# EasyEDA_Schematic_Split_Flap_Controller_.net
KiCad netlist of a schematic drawn in EasyEDA
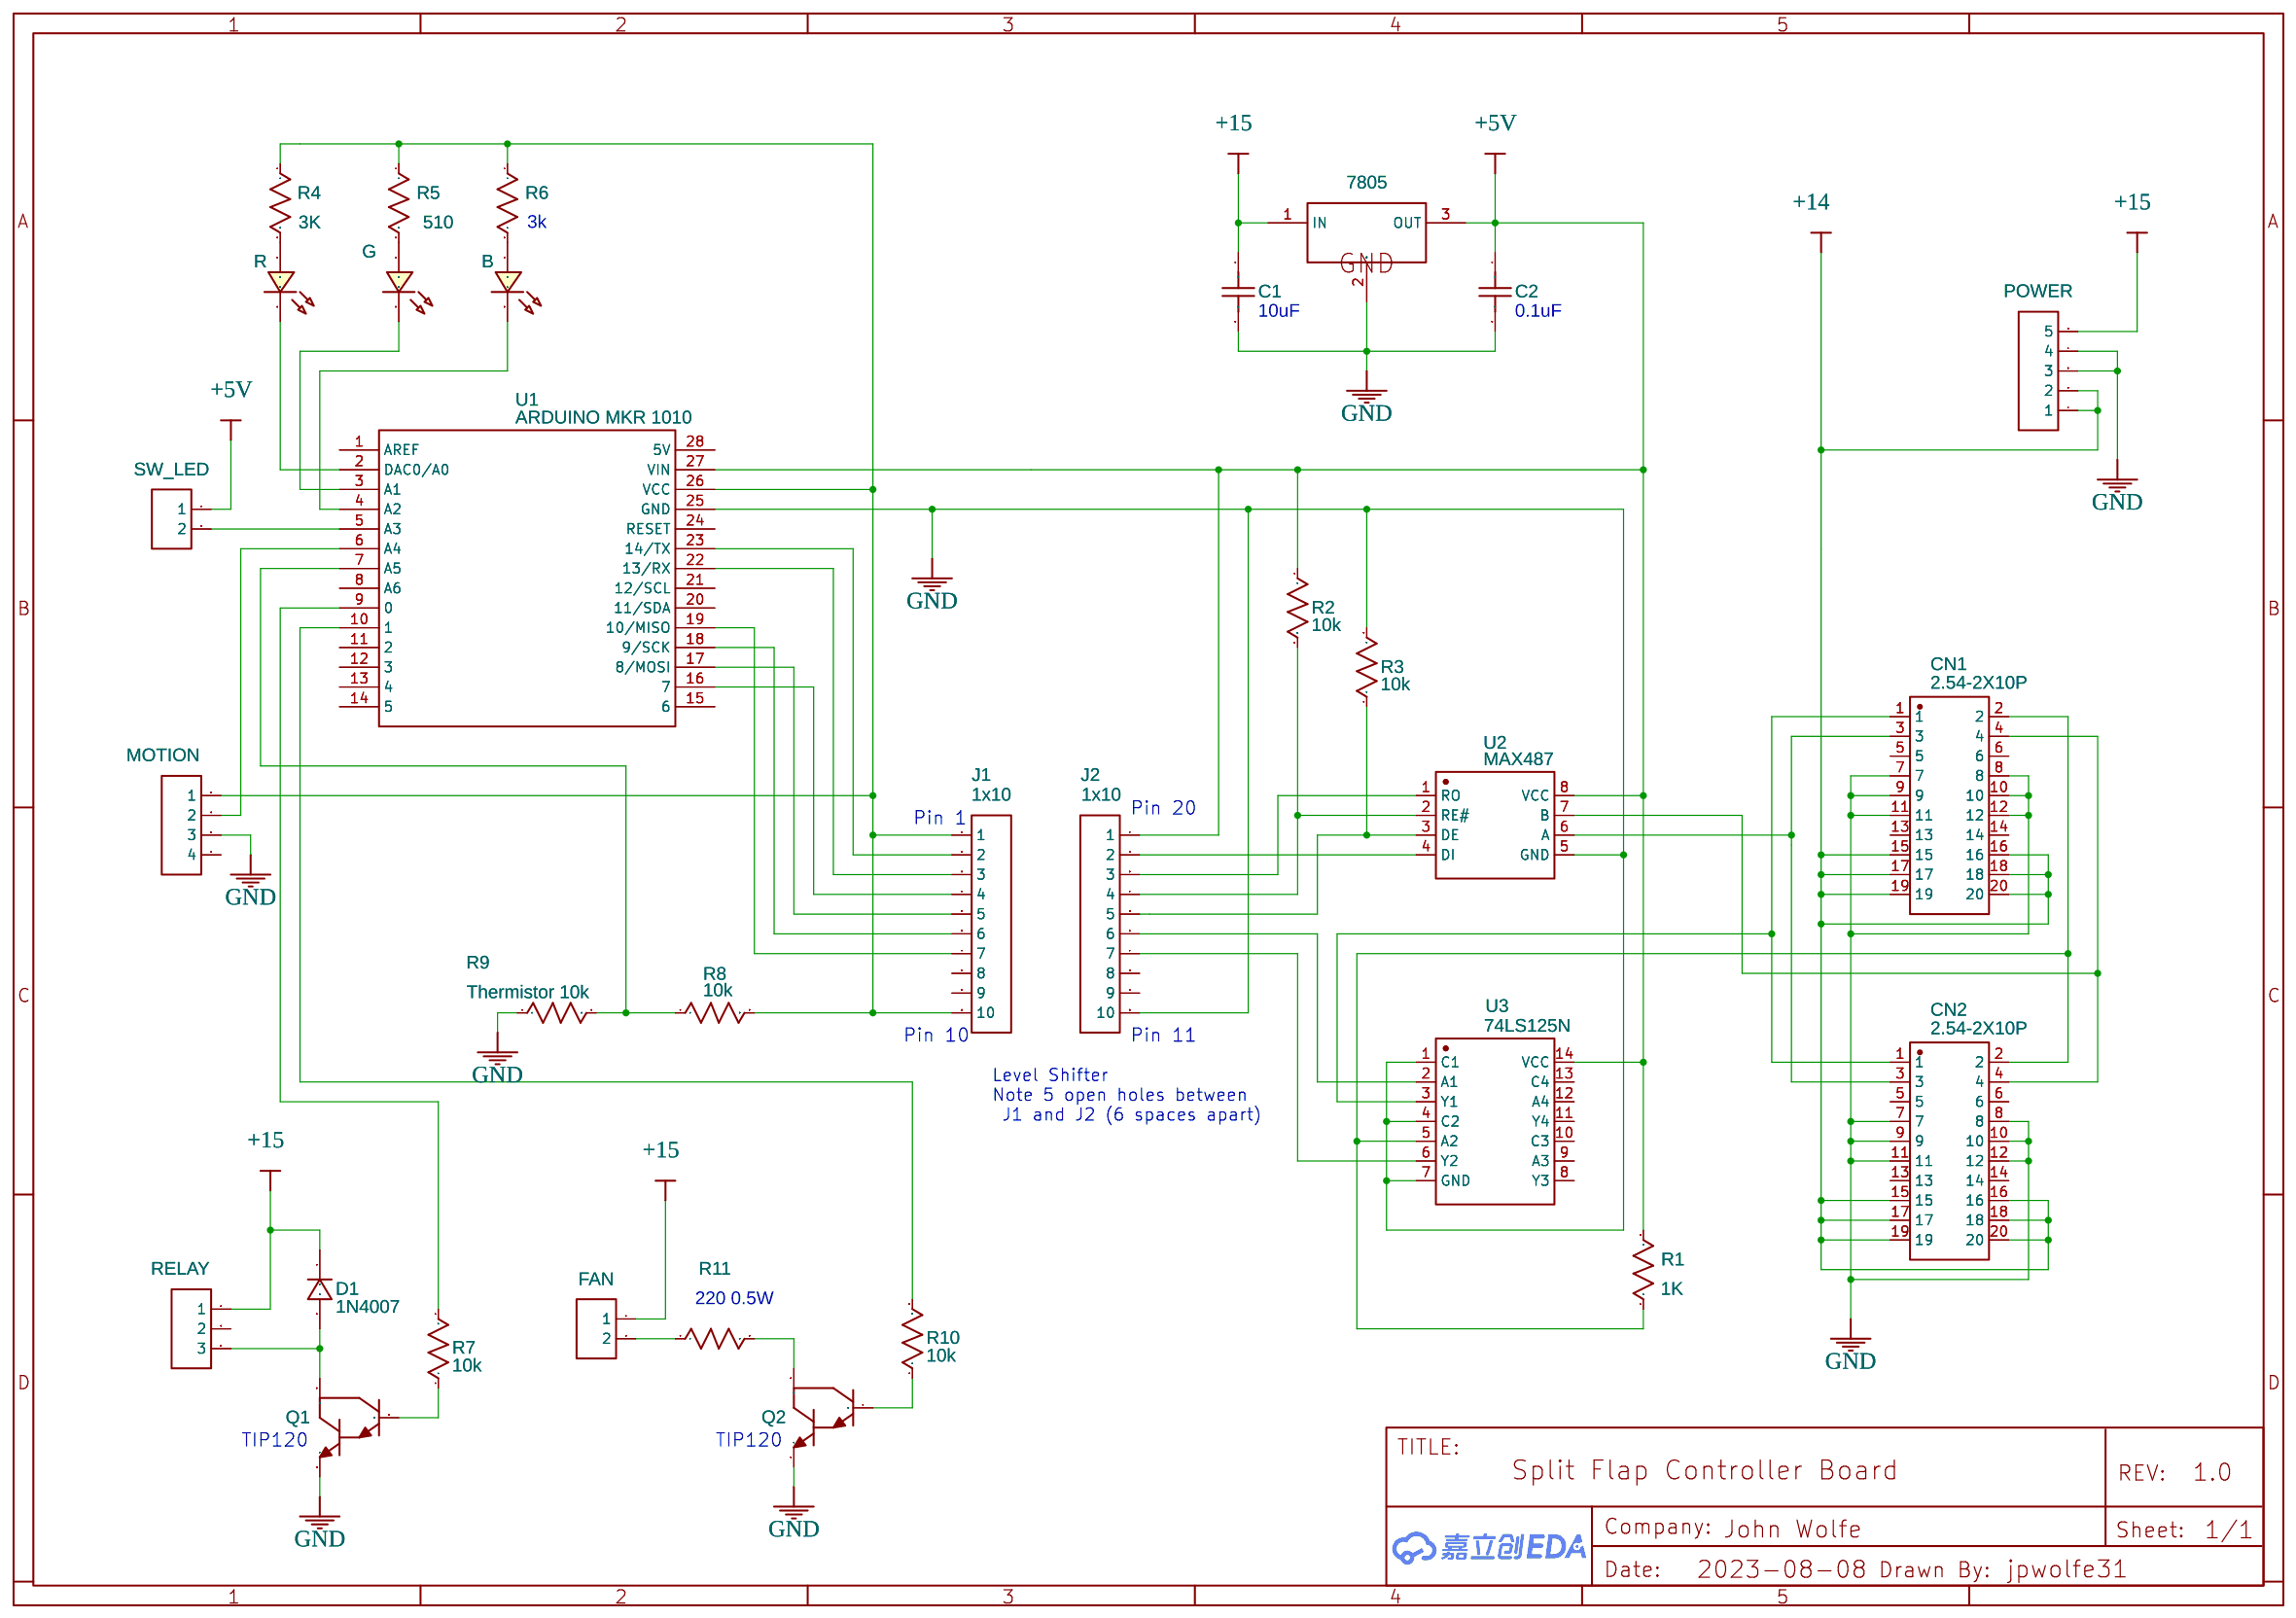
[diagram p0: schematic sheet]

(export (version "E")
  (design (tool "Eeschema 10.0.6"))
  (components
    (comp (ref "1K") (value "R1") (libsource (lib "") (part "R_AXIAL-0.3_US_5")))
    (comp (ref "3K") (value "R5") (libsource (lib "") (part "R_AXIAL-0.3_US_2")))
    (comp (ref "510") (value "R4") (libsource (lib "") (part "R_AXIAL-0.3_US_3")))
    (comp (ref "7805")
      (value "7805")
      (fields
        (field (name "Manufacturer Part") "L7805CV-DG")
        (field (name "Manufacturer") "STMicroelectronics")
      )
      (libsource (lib "") (part "7805(TO-220)"))
    )
    (comp (ref "B")
      (value "LED-TH-3mm_B")
      (fields
        (field (name "Manufacturer Part") "204-10SUBC/S400-A4")
        (field (name "Manufacturer") "EVERLIGHT(台湾亿光)")
      )
      (libsource (lib "") (part "LED-TH-3mm_B"))
    )
    (comp (ref "C1") (value "1u") (libsource (lib "") (part "C_RAD-0.1_US")))
    (comp (ref "C2") (value "1u") (libsource (lib "") (part "C_RAD-0.1_US")))
    (comp (ref "CN1")
      (value "2.54-2X10P")
      (fields
        (field (name "Manufacturer Part") "KH-DC3-2.54-2X10P")
        (field (name "Manufacturer") "kinghelm(金航标)")
      )
      (libsource (lib "") (part "KH-DC3-2.54-2X10P"))
    )
    (comp (ref "CN2")
      (value "2.54-2X10P")
      (fields
        (field (name "Manufacturer Part") "KH-DC3-2.54-2X10P")
        (field (name "Manufacturer") "kinghelm(金航标)")
      )
      (libsource (lib "") (part "KH-DC3-2.54-2X10P"))
    )
    (comp (ref "D1")
      (value "1N4007")
      (fields (field (name "Manufacturer Part") "1N4148") (field (name "Manufacturer") "STMicroelectronics"))
      (libsource (lib "") (part "1N4148"))
    )
    (comp (ref "FAN") (value "HDR-M-2.54_1x2") (libsource (lib "") (part "HDR-M-2.54_1x2_1")))
    (comp (ref "G")
      (value "LED-TH-3mm_G")
      (fields
        (field (name "Manufacturer Part") "204-10SYGD/S530-E3")
        (field (name "Manufacturer") "EVERLIGHT(台湾亿光)")
      )
      (libsource (lib "") (part "LED-TH-3mm_G"))
    )
    (comp (ref "J1")
      (value "1x10")
      (fields (field (name "Manufacturer") "BOOMELE(博穆精密)"))
      (libsource (lib "") (part "Header-Female-2.54_1x10"))
    )
    (comp (ref "J2")
      (value "1x10")
      (fields (field (name "Manufacturer") "BOOMELE(博穆精密)"))
      (libsource (lib "") (part "Header-Female-2.54_1x10_1"))
    )
    (comp (ref "MOTION") (value "HDR-M-2.54_1x4") (libsource (lib "") (part "HDR-M-2.54_1x4")))
    (comp (ref "POWER") (value "CN3") (libsource (lib "") (part "HDR-F-2.54_1x5")))
    (comp (ref "Q1")
      (value "Q1")
      (fields (field (name "Manufacturer") "CJ(江苏长电/长晶)"))
      (libsource (lib "") (part "TIP122_C84073"))
    )
    (comp (ref "Q2")
      (value "TIP120")
      (fields (field (name "Manufacturer") "CJ(江苏长电/长晶)"))
      (libsource (lib "") (part "TIP122_C84073"))
    )
    (comp (ref "R")
      (value "LED-TH-3mm_R")
      (fields
        (field (name "Manufacturer Part") "204-10SDRD/S530-A3-L")
        (field (name "Manufacturer") "EVERLIGHT(台湾亿光)")
      )
      (libsource (lib "") (part "LED-TH-3mm_R"))
    )
    (comp (ref "R2") (value "10k") (libsource (lib "") (part "R_AXIAL-0.3_US_1")))
    (comp (ref "R3") (value "10k") (libsource (lib "") (part "R_AXIAL-0.3_US_4")))
    (comp (ref "R6") (value "R6") (libsource (lib "") (part "R_AXIAL-0.3_US_1")))
    (comp (ref "R7") (value "10k") (libsource (lib "") (part "R_AXIAL-0.3_US_4")))
    (comp (ref "R8") (value "10k") (libsource (lib "") (part "R_AXIAL-0.3_US")))
    (comp (ref "R9") (value "Thermistor 10k") (libsource (lib "") (part "R_AXIAL-0.3_US")))
    (comp (ref "R10") (value "10k") (libsource (lib "") (part "R_AXIAL-0.3_US_4")))
    (comp (ref "R11") (value "R11") (libsource (lib "") (part "R_AXIAL-0.4_US")))
    (comp (ref "RELAY") (value "HDR-M-2.54_1x3") (libsource (lib "") (part "HDR-M-2.54_1x3")))
    (comp (ref "SW_LED") (value "HDR-M-2.54_1x2") (libsource (lib "") (part "HDR-M-2.54_1x2")))
    (comp (ref "U1") (value "ARDUINO MKR 1010") (libsource (lib "") (part "ARDUINO MKR 1010")))
    (comp (ref "U2")
      (value "MAX487")
      (fields (field (name "Manufacturer") "MAXIM"))
      (libsource (lib "") (part "MAX487CPA"))
    )
    (comp (ref "U3") (value "74LS125N") (libsource (lib "") (part "74LS125N")))
  )
  (nets
    (net (code "1") (name "+5V") (class "Default")
      (node (ref "1K") (pin "2") (pinfunction "2_2") (pintype "unspecified"))
      (node (ref "7805") (pin "3") (pinfunction "OUT_3") (pintype "passive"))
      (node (ref "C2") (pin "1") (pinfunction "1_1") (pintype "unspecified"))
      (node (ref "J2") (pin "1") (pinfunction "1_1") (pintype "input"))
      (node (ref "R2") (pin "1") (pinfunction "1_1") (pintype "unspecified"))
      (node (ref "SW_LED") (pin "1") (pinfunction "1_1") (pintype "unspecified"))
      (node (ref "U1") (pin "27") (pinfunction "VIN_27") (pintype "unspecified"))
      (node (ref "U2") (pin "8") (pinfunction "VCC_8") (pintype "unspecified"))
      (node (ref "U3") (pin "14") (pinfunction "VCC_14") (pintype "unspecified"))
    )
    (net (code "2") (name "+14") (class "Default")
      (node (ref "CN1") (pin "15") (pinfunction "15_15") (pintype "unspecified"))
      (node (ref "CN1") (pin "16") (pinfunction "16_16") (pintype "unspecified"))
      (node (ref "CN1") (pin "17") (pinfunction "17_17") (pintype "unspecified"))
      (node (ref "CN1") (pin "18") (pinfunction "18_18") (pintype "unspecified"))
      (node (ref "CN1") (pin "19") (pinfunction "19_19") (pintype "unspecified"))
      (node (ref "CN1") (pin "20") (pinfunction "20_20") (pintype "unspecified"))
      (node (ref "CN2") (pin "15") (pinfunction "15_15") (pintype "unspecified"))
      (node (ref "CN2") (pin "16") (pinfunction "16_16") (pintype "unspecified"))
      (node (ref "CN2") (pin "17") (pinfunction "17_17") (pintype "unspecified"))
      (node (ref "CN2") (pin "18") (pinfunction "18_18") (pintype "unspecified"))
      (node (ref "CN2") (pin "19") (pinfunction "19_19") (pintype "unspecified"))
      (node (ref "CN2") (pin "20") (pinfunction "20_20") (pintype "unspecified"))
      (node (ref "POWER") (pin "1") (pinfunction "1_1") (pintype "unspecified"))
      (node (ref "POWER") (pin "2") (pinfunction "2_2") (pintype "unspecified"))
    )
    (net (code "3") (name "+15") (class "Default")
      (node (ref "7805") (pin "1") (pinfunction "IN_1") (pintype "passive"))
      (node (ref "C1") (pin "1") (pinfunction "1_1") (pintype "unspecified"))
      (node (ref "D1") (pin "1") (pinfunction "1_1") (pintype "unspecified"))
      (node (ref "FAN") (pin "1") (pinfunction "1_1") (pintype "unspecified"))
      (node (ref "POWER") (pin "5") (pinfunction "5_5") (pintype "unspecified"))
      (node (ref "RELAY") (pin "1") (pinfunction "1_1") (pintype "input"))
    )
    (net (code "4") (name "GND") (class "Default")
      (node (ref "7805") (pin "2") (pinfunction "GND_2") (pintype "passive"))
      (node (ref "C1") (pin "2") (pinfunction "2_2") (pintype "unspecified"))
      (node (ref "C2") (pin "2") (pinfunction "2_2") (pintype "unspecified"))
      (node (ref "CN1") (pin "10") (pinfunction "10_10") (pintype "unspecified"))
      (node (ref "CN1") (pin "11") (pinfunction "11_11") (pintype "unspecified"))
      (node (ref "CN1") (pin "12") (pinfunction "12_12") (pintype "unspecified"))
      (node (ref "CN1") (pin "7") (pinfunction "7_7") (pintype "unspecified"))
      (node (ref "CN1") (pin "8") (pinfunction "8_8") (pintype "unspecified"))
      (node (ref "CN1") (pin "9") (pinfunction "9_9") (pintype "unspecified"))
      (node (ref "CN2") (pin "10") (pinfunction "10_10") (pintype "unspecified"))
      (node (ref "CN2") (pin "11") (pinfunction "11_11") (pintype "unspecified"))
      (node (ref "CN2") (pin "12") (pinfunction "12_12") (pintype "unspecified"))
      (node (ref "CN2") (pin "7") (pinfunction "7_7") (pintype "unspecified"))
      (node (ref "CN2") (pin "8") (pinfunction "8_8") (pintype "unspecified"))
      (node (ref "CN2") (pin "9") (pinfunction "9_9") (pintype "unspecified"))
      (node (ref "J2") (pin "10") (pinfunction "10_10") (pintype "input"))
      (node (ref "MOTION") (pin "3") (pinfunction "3_3") (pintype "unspecified"))
      (node (ref "POWER") (pin "3") (pinfunction "3_3") (pintype "unspecified"))
      (node (ref "POWER") (pin "4") (pinfunction "4_4") (pintype "unspecified"))
      (node (ref "Q1") (pin "3") (pinfunction "E_3") (pintype "unspecified"))
      (node (ref "Q2") (pin "3") (pinfunction "E_3") (pintype "unspecified"))
      (node (ref "R3") (pin "2") (pinfunction "2_2") (pintype "unspecified"))
      (node (ref "R9") (pin "1") (pinfunction "1_1") (pintype "unspecified"))
      (node (ref "U1") (pin "25") (pinfunction "GND_25") (pintype "unspecified"))
      (node (ref "U2") (pin "5") (pinfunction "GND_5") (pintype "unspecified"))
      (node (ref "U3") (pin "1") (pinfunction "C1_1") (pintype "unspecified"))
      (node (ref "U3") (pin "4") (pinfunction "C2_4") (pintype "unspecified"))
      (node (ref "U3") (pin "7") (pinfunction "GND_7") (pintype "unspecified"))
    )
    (net (code "5") (name "Net-(3K-Pad2)") (class "Default")
      (node (ref "3K") (pin "2") (pinfunction "2_2") (pintype "unspecified"))
      (node (ref "G") (pin "1") (pinfunction "1_1") (pintype "unspecified"))
    )
    (net (code "6") (name "Net-(510-Pad2)") (class "Default")
      (node (ref "510") (pin "2") (pinfunction "2_2") (pintype "unspecified"))
      (node (ref "R") (pin "1") (pinfunction "1_1") (pintype "unspecified"))
    )
    (net (code "7") (name "Net-(B-Pad1)") (class "Default")
      (node (ref "B") (pin "1") (pinfunction "1_1") (pintype "unspecified"))
      (node (ref "R6") (pin "2") (pinfunction "2_2") (pintype "unspecified"))
    )
    (net (code "8") (name "Net-(FAN-Pad2)") (class "Default")
      (node (ref "FAN") (pin "2") (pinfunction "2_2") (pintype "unspecified"))
      (node (ref "R11") (pin "1") (pinfunction "1_1") (pintype "unspecified"))
    )
    (net (code "9") (name "Net-(Q1-B)") (class "Default")
      (node (ref "Q1") (pin "1") (pinfunction "B_1") (pintype "unspecified"))
      (node (ref "R7") (pin "1") (pinfunction "1_1") (pintype "unspecified"))
    )
    (net (code "10") (name "Net-(Q1-C)") (class "Default")
      (node (ref "D1") (pin "2") (pinfunction "2_2") (pintype "unspecified"))
      (node (ref "Q1") (pin "2") (pinfunction "C_2") (pintype "unspecified"))
      (node (ref "RELAY") (pin "3") (pinfunction "3_3") (pintype "input"))
    )
    (net (code "11") (name "Net-(Q2-B)") (class "Default")
      (node (ref "Q2") (pin "1") (pinfunction "B_1") (pintype "unspecified"))
      (node (ref "R10") (pin "1") (pinfunction "1_1") (pintype "unspecified"))
    )
    (net (code "12") (name "Net-(Q2-C)") (class "Default")
      (node (ref "Q2") (pin "2") (pinfunction "C_2") (pintype "unspecified"))
      (node (ref "R11") (pin "2") (pinfunction "2_2") (pintype "unspecified"))
    )
    (net (code "13") (name "Net-(U1-0)") (class "Default")
      (node (ref "R7") (pin "2") (pinfunction "2_2") (pintype "unspecified"))
      (node (ref "U1") (pin "9") (pinfunction "0_9") (pintype "unspecified"))
    )
    (net (code "14") (name "Net-(U1-1)") (class "Default")
      (node (ref "R10") (pin "2") (pinfunction "2_2") (pintype "unspecified"))
      (node (ref "U1") (pin "10") (pinfunction "1_10") (pintype "unspecified"))
    )
    (net (code "15") (name "Net-(U1-7)") (class "Default")
      (node (ref "J1") (pin "4") (pinfunction "4_4") (pintype "input"))
      (node (ref "U1") (pin "16") (pinfunction "7_16") (pintype "unspecified"))
    )
    (net (code "16") (name "Net-(U1-8{slash}MOSI)") (class "Default")
      (node (ref "J1") (pin "5") (pinfunction "5_5") (pintype "input"))
      (node (ref "U1") (pin "17") (pinfunction "8/MOSI_17") (pintype "unspecified"))
    )
    (net (code "17") (name "Net-(U1-9{slash}SCK)") (class "Default")
      (node (ref "J1") (pin "6") (pinfunction "6_6") (pintype "input"))
      (node (ref "U1") (pin "18") (pinfunction "9/SCK_18") (pintype "unspecified"))
    )
    (net (code "18") (name "Net-(U1-10{slash}MISO)") (class "Default")
      (node (ref "J1") (pin "7") (pinfunction "7_7") (pintype "input"))
      (node (ref "U1") (pin "19") (pinfunction "10/MISO_19") (pintype "unspecified"))
    )
    (net (code "19") (name "Net-(U1-13{slash}RX)") (class "Default")
      (node (ref "J1") (pin "3") (pinfunction "3_3") (pintype "input"))
      (node (ref "U1") (pin "22") (pinfunction "13/RX_22") (pintype "unspecified"))
    )
    (net (code "20") (name "Net-(U1-14{slash}TX)") (class "Default")
      (node (ref "J1") (pin "2") (pinfunction "2_2") (pintype "input"))
      (node (ref "U1") (pin "23") (pinfunction "14/TX_23") (pintype "unspecified"))
    )
    (net (code "21") (name "Net-(U1-A1)") (class "Default")
      (node (ref "G") (pin "2") (pinfunction "2_2") (pintype "unspecified"))
      (node (ref "U1") (pin "3") (pinfunction "A1_3") (pintype "unspecified"))
    )
    (net (code "22") (name "Net-(U1-A2)") (class "Default")
      (node (ref "B") (pin "2") (pinfunction "2_2") (pintype "unspecified"))
      (node (ref "U1") (pin "4") (pinfunction "A2_4") (pintype "unspecified"))
    )
    (net (code "23") (name "Net-(U1-A3)") (class "Default")
      (node (ref "SW_LED") (pin "2") (pinfunction "2_2") (pintype "unspecified"))
      (node (ref "U1") (pin "5") (pinfunction "A3_5") (pintype "unspecified"))
    )
    (net (code "24") (name "Net-(U1-A4)") (class "Default")
      (node (ref "MOTION") (pin "2") (pinfunction "2_2") (pintype "unspecified"))
      (node (ref "U1") (pin "6") (pinfunction "A4_6") (pintype "unspecified"))
    )
    (net (code "25") (name "Net-(U1-A5)") (class "Default")
      (node (ref "R8") (pin "1") (pinfunction "1_1") (pintype "unspecified"))
      (node (ref "R9") (pin "2") (pinfunction "2_2") (pintype "unspecified"))
      (node (ref "U1") (pin "7") (pinfunction "A5_7") (pintype "unspecified"))
    )
    (net (code "26") (name "Net-(U1-DAC0{slash}A0)") (class "Default")
      (node (ref "R") (pin "2") (pinfunction "2_2") (pintype "unspecified"))
      (node (ref "U1") (pin "2") (pinfunction "DAC0/A0_2") (pintype "unspecified"))
    )
    (net (code "27") (name "Net-(U1-VCC)") (class "Default")
      (node (ref "3K") (pin "1") (pinfunction "1_1") (pintype "unspecified"))
      (node (ref "510") (pin "1") (pinfunction "1_1") (pintype "unspecified"))
      (node (ref "J1") (pin "1") (pinfunction "1_1") (pintype "input"))
      (node (ref "J1") (pin "10") (pinfunction "10_10") (pintype "input"))
      (node (ref "MOTION") (pin "1") (pinfunction "1_1") (pintype "unspecified"))
      (node (ref "R6") (pin "1") (pinfunction "1_1") (pintype "unspecified"))
      (node (ref "R8") (pin "2") (pinfunction "2_2") (pintype "unspecified"))
      (node (ref "U1") (pin "26") (pinfunction "VCC_26") (pintype "unspecified"))
    )
    (net (code "28") (name "Net-(U2-A)") (class "Default")
      (node (ref "CN1") (pin "3") (pinfunction "3_3") (pintype "unspecified"))
      (node (ref "CN2") (pin "3") (pinfunction "3_3") (pintype "unspecified"))
      (node (ref "U2") (pin "6") (pinfunction "A_6") (pintype "unspecified"))
    )
    (net (code "29") (name "Net-(U2-B)") (class "Default")
      (node (ref "CN1") (pin "4") (pinfunction "4_4") (pintype "unspecified"))
      (node (ref "CN2") (pin "4") (pinfunction "4_4") (pintype "unspecified"))
      (node (ref "U2") (pin "7") (pinfunction "B_7") (pintype "unspecified"))
    )
    (net (code "30") (name "Net-(U2-DE)") (class "Default")
      (node (ref "J2") (pin "5") (pinfunction "5_5") (pintype "input"))
      (node (ref "R3") (pin "1") (pinfunction "1_1") (pintype "unspecified"))
      (node (ref "U2") (pin "3") (pinfunction "DE_3") (pintype "unspecified"))
    )
    (net (code "31") (name "Net-(U2-DI)") (class "Default")
      (node (ref "J2") (pin "2") (pinfunction "2_2") (pintype "input"))
      (node (ref "U2") (pin "4") (pinfunction "DI_4") (pintype "unspecified"))
    )
    (net (code "32") (name "Net-(U2-RE#)") (class "Default")
      (node (ref "J2") (pin "4") (pinfunction "4_4") (pintype "input"))
      (node (ref "R2") (pin "2") (pinfunction "2_2") (pintype "unspecified"))
      (node (ref "U2") (pin "2") (pinfunction "RE#_2") (pintype "unspecified"))
    )
    (net (code "33") (name "Net-(U2-RO)") (class "Default")
      (node (ref "J2") (pin "3") (pinfunction "3_3") (pintype "input"))
      (node (ref "U2") (pin "1") (pinfunction "RO_1") (pintype "unspecified"))
    )
    (net (code "34") (name "Net-(U3-A1)") (class "Default")
      (node (ref "J2") (pin "6") (pinfunction "6_6") (pintype "input"))
      (node (ref "U3") (pin "2") (pinfunction "A1_2") (pintype "unspecified"))
    )
    (net (code "35") (name "Net-(U3-A2)") (class "Default")
      (node (ref "1K") (pin "1") (pinfunction "1_1") (pintype "unspecified"))
      (node (ref "CN1") (pin "2") (pinfunction "2_2") (pintype "unspecified"))
      (node (ref "CN2") (pin "2") (pinfunction "2_2") (pintype "unspecified"))
      (node (ref "U3") (pin "5") (pinfunction "A2_5") (pintype "unspecified"))
    )
    (net (code "36") (name "Net-(U3-Y1)") (class "Default")
      (node (ref "CN1") (pin "1") (pinfunction "1_1") (pintype "unspecified"))
      (node (ref "CN2") (pin "1") (pinfunction "1_1") (pintype "unspecified"))
      (node (ref "U3") (pin "3") (pinfunction "Y1_3") (pintype "unspecified"))
    )
    (net (code "37") (name "Net-(U3-Y2)") (class "Default")
      (node (ref "J2") (pin "7") (pinfunction "7_7") (pintype "input"))
      (node (ref "U3") (pin "6") (pinfunction "Y2_6") (pintype "unspecified"))
    )
    (net (code "38") (name "unconnected-(CN1-Pad5)") (class "Default")
      (node (ref "CN1") (pin "5") (pinfunction "5_5") (pintype "unspecified"))
    )
    (net (code "39") (name "unconnected-(CN1-Pad6)") (class "Default")
      (node (ref "CN1") (pin "6") (pinfunction "6_6") (pintype "unspecified"))
    )
    (net (code "40") (name "unconnected-(CN1-Pad13)") (class "Default")
      (node (ref "CN1") (pin "13") (pinfunction "13_13") (pintype "unspecified"))
    )
    (net (code "41") (name "unconnected-(CN1-Pad14)") (class "Default")
      (node (ref "CN1") (pin "14") (pinfunction "14_14") (pintype "unspecified"))
    )
    (net (code "42") (name "unconnected-(CN2-Pad5)") (class "Default")
      (node (ref "CN2") (pin "5") (pinfunction "5_5") (pintype "unspecified"))
    )
    (net (code "43") (name "unconnected-(CN2-Pad6)") (class "Default")
      (node (ref "CN2") (pin "6") (pinfunction "6_6") (pintype "unspecified"))
    )
    (net (code "44") (name "unconnected-(CN2-Pad13)") (class "Default")
      (node (ref "CN2") (pin "13") (pinfunction "13_13") (pintype "unspecified"))
    )
    (net (code "45") (name "unconnected-(CN2-Pad14)") (class "Default")
      (node (ref "CN2") (pin "14") (pinfunction "14_14") (pintype "unspecified"))
    )
    (net (code "46") (name "unconnected-(J1-Pad8)") (class "Default")
      (node (ref "J1") (pin "8") (pinfunction "8_8") (pintype "input"))
    )
    (net (code "47") (name "unconnected-(J1-Pad9)") (class "Default")
      (node (ref "J1") (pin "9") (pinfunction "9_9") (pintype "input"))
    )
    (net (code "48") (name "unconnected-(J2-Pad8)") (class "Default")
      (node (ref "J2") (pin "8") (pinfunction "8_8") (pintype "input"))
    )
    (net (code "49") (name "unconnected-(J2-Pad9)") (class "Default")
      (node (ref "J2") (pin "9") (pinfunction "9_9") (pintype "input"))
    )
    (net (code "50") (name "unconnected-(MOTION-Pad4)") (class "Default")
      (node (ref "MOTION") (pin "4") (pinfunction "4_4") (pintype "unspecified"))
    )
    (net (code "51") (name "unconnected-(RELAY-Pad2)") (class "Default")
      (node (ref "RELAY") (pin "2") (pinfunction "2_2") (pintype "input"))
    )
    (net (code "52") (name "unconnected-(U1-2-Pad11)") (class "Default")
      (node (ref "U1") (pin "11") (pinfunction "2_11") (pintype "unspecified"))
    )
    (net (code "53") (name "unconnected-(U1-3-Pad12)") (class "Default")
      (node (ref "U1") (pin "12") (pinfunction "3_12") (pintype "unspecified"))
    )
    (net (code "54") (name "unconnected-(U1-4-Pad13)") (class "Default")
      (node (ref "U1") (pin "13") (pinfunction "4_13") (pintype "unspecified"))
    )
    (net (code "55") (name "unconnected-(U1-5-Pad14)") (class "Default")
      (node (ref "U1") (pin "14") (pinfunction "5_14") (pintype "unspecified"))
    )
    (net (code "56") (name "unconnected-(U1-5V-Pad28)") (class "Default")
      (node (ref "U1") (pin "28") (pinfunction "5V_28") (pintype "unspecified"))
    )
    (net (code "57") (name "unconnected-(U1-6-Pad15)") (class "Default")
      (node (ref "U1") (pin "15") (pinfunction "6_15") (pintype "unspecified"))
    )
    (net (code "58") (name "unconnected-(U1-11{slash}SDA-Pad20)") (class "Default")
      (node (ref "U1") (pin "20") (pinfunction "11/SDA_20") (pintype "unspecified"))
    )
    (net (code "59") (name "unconnected-(U1-12{slash}SCL-Pad21)") (class "Default")
      (node (ref "U1") (pin "21") (pinfunction "12/SCL_21") (pintype "unspecified"))
    )
    (net (code "60") (name "unconnected-(U1-A6-Pad8)") (class "Default")
      (node (ref "U1") (pin "8") (pinfunction "A6_8") (pintype "unspecified"))
    )
    (net (code "61") (name "unconnected-(U1-AREF-Pad1)") (class "Default")
      (node (ref "U1") (pin "1") (pinfunction "AREF_1") (pintype "unspecified"))
    )
    (net (code "62") (name "unconnected-(U1-RESET-Pad24)") (class "Default")
      (node (ref "U1") (pin "24") (pinfunction "RESET_24") (pintype "unspecified"))
    )
    (net (code "63") (name "unconnected-(U3-A3-Pad9)") (class "Default")
      (node (ref "U3") (pin "9") (pinfunction "A3_9") (pintype "unspecified"))
    )
    (net (code "64") (name "unconnected-(U3-A4-Pad12)") (class "Default")
      (node (ref "U3") (pin "12") (pinfunction "A4_12") (pintype "unspecified"))
    )
    (net (code "65") (name "unconnected-(U3-C3-Pad10)") (class "Default")
      (node (ref "U3") (pin "10") (pinfunction "C3_10") (pintype "unspecified"))
    )
    (net (code "66") (name "unconnected-(U3-C4-Pad13)") (class "Default")
      (node (ref "U3") (pin "13") (pinfunction "C4_13") (pintype "unspecified"))
    )
    (net (code "67") (name "unconnected-(U3-Y3-Pad8)") (class "Default")
      (node (ref "U3") (pin "8") (pinfunction "Y3_8") (pintype "unspecified"))
    )
    (net (code "68") (name "unconnected-(U3-Y4-Pad11)") (class "Default")
      (node (ref "U3") (pin "11") (pinfunction "Y4_11") (pintype "unspecified"))
    )
  )
)
